# PCM2912_CODEC_MAIN.net
KiCad netlist of a schematic drawn in Altium Designer
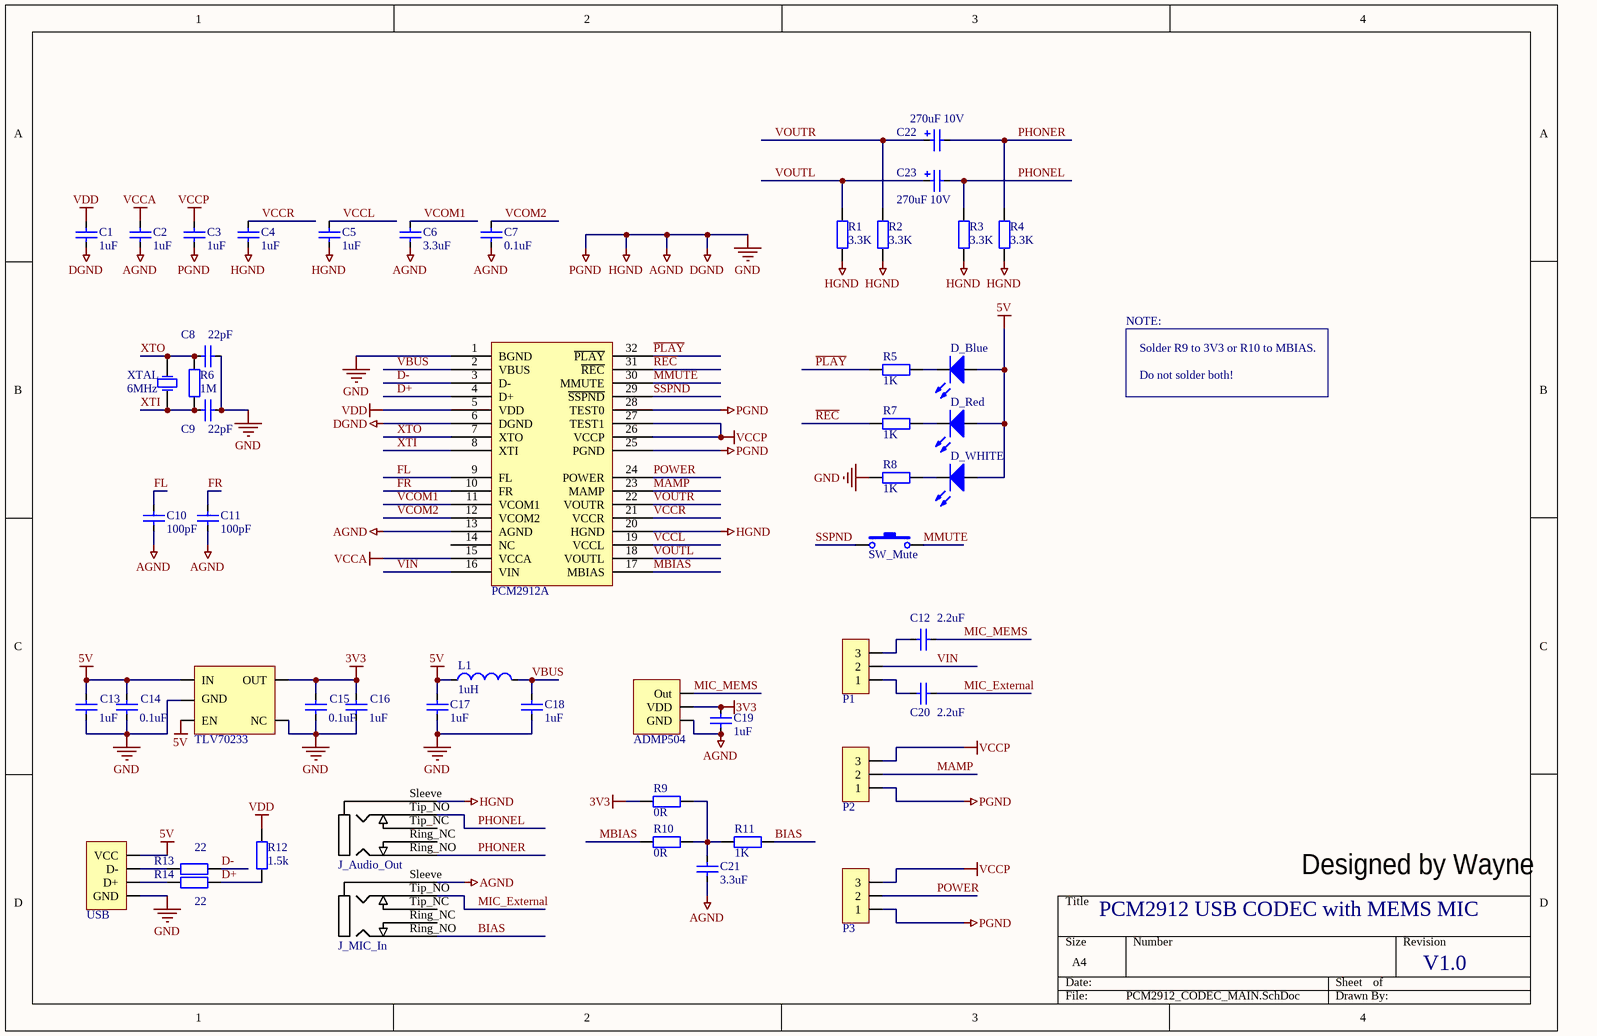
[diagram p0: PCM2912_CODEC_MAIN.SchDoc]

(export (version "E")
  (design (tool "Eeschema 10.0.6"))
  (components
    (comp (ref "ADMP504")
      (value "ADMP504")
      (footprint "PCB_IC:ADMP504")
      (description "ADMP504 Analog Output MEMS Microphone")
      (libsource (lib "SCH_IC") (part "ADMP504"))
    )
    (comp (ref "C1")
      (value "1uF")
      (footprint "PCB_Passive:CAP_0603")
      (description "Capacitor")
      (fields (field (name "Comment") "Cap_0603"))
      (libsource (lib "SCH_Passive") (part "Cap_0603"))
    )
    (comp (ref "C2")
      (value "1uF")
      (footprint "PCB_Passive:CAP_0603")
      (description "Capacitor")
      (fields (field (name "Comment") "Cap_0603"))
      (libsource (lib "SCH_Passive") (part "Cap_0603"))
    )
    (comp (ref "C3")
      (value "1uF")
      (footprint "PCB_Passive:CAP_0603")
      (description "Capacitor")
      (fields (field (name "Comment") "Cap_0603"))
      (libsource (lib "SCH_Passive") (part "Cap_0603"))
    )
    (comp (ref "C4")
      (value "1uF")
      (footprint "PCB_Passive:CAP_0603")
      (description "Capacitor")
      (fields (field (name "Comment") "Cap_0603"))
      (libsource (lib "SCH_Passive") (part "Cap_0603"))
    )
    (comp (ref "C5")
      (value "1uF")
      (footprint "PCB_Passive:CAP_0603")
      (description "Capacitor")
      (fields (field (name "Comment") "Cap_0603"))
      (libsource (lib "SCH_Passive") (part "Cap_0603"))
    )
    (comp (ref "C6")
      (value "3.3uF")
      (footprint "PCB_Passive:CAP_0603")
      (description "Capacitor")
      (fields (field (name "Comment") "Cap_0603"))
      (libsource (lib "SCH_Passive") (part "Cap_0603"))
    )
    (comp (ref "C7")
      (value "0.1uF")
      (footprint "PCB_Passive:CAP_0603")
      (description "Capacitor")
      (fields (field (name "Comment") "Cap_0603"))
      (libsource (lib "SCH_Passive") (part "Cap_0603"))
    )
    (comp (ref "C8")
      (value "22pF")
      (footprint "PCB_Passive:CAP_0603")
      (description "Capacitor")
      (fields (field (name "Comment") "Cap_0603"))
      (libsource (lib "SCH_Passive") (part "Cap_0603"))
    )
    (comp (ref "C9")
      (value "22pF")
      (footprint "PCB_Passive:CAP_0603")
      (description "Capacitor")
      (fields (field (name "Comment") "Cap_0603"))
      (libsource (lib "SCH_Passive") (part "Cap_0603"))
    )
    (comp (ref "C10")
      (value "100pF")
      (footprint "PCB_Passive:CAP_0603")
      (description "Capacitor")
      (fields (field (name "Comment") "Cap_0603"))
      (libsource (lib "SCH_Passive") (part "Cap_0603"))
    )
    (comp (ref "C11")
      (value "100pF")
      (footprint "PCB_Passive:CAP_0603")
      (description "Capacitor")
      (fields (field (name "Comment") "Cap_0603"))
      (libsource (lib "SCH_Passive") (part "Cap_0603"))
    )
    (comp (ref "C12")
      (value "2.2uF")
      (footprint "PCB_Passive:CAP_0603")
      (description "Capacitor")
      (fields (field (name "Comment") "Cap_0603"))
      (libsource (lib "SCH_Passive") (part "Cap_0603"))
    )
    (comp (ref "C13")
      (value "1uF")
      (footprint "PCB_Passive:CAP_0603")
      (description "Capacitor")
      (fields (field (name "Comment") "Cap_0603"))
      (libsource (lib "SCH_Passive") (part "Cap_0603"))
    )
    (comp (ref "C14")
      (value "0.1uF")
      (footprint "PCB_Passive:CAP_0603")
      (description "Capacitor")
      (fields (field (name "Comment") "Cap_0603"))
      (libsource (lib "SCH_Passive") (part "Cap_0603"))
    )
    (comp (ref "C15")
      (value "0.1uF")
      (footprint "PCB_Passive:CAP_0603")
      (description "Capacitor")
      (fields (field (name "Comment") "Cap_0603"))
      (libsource (lib "SCH_Passive") (part "Cap_0603"))
    )
    (comp (ref "C16")
      (value "1uF")
      (footprint "PCB_Passive:CAP_0603")
      (description "Capacitor")
      (fields (field (name "Comment") "Cap_0603"))
      (libsource (lib "SCH_Passive") (part "Cap_0603"))
    )
    (comp (ref "C17")
      (value "1uF")
      (footprint "PCB_Passive:CAP_0603")
      (description "Capacitor")
      (fields (field (name "Comment") "Cap_0603"))
      (libsource (lib "SCH_Passive") (part "Cap_0603"))
    )
    (comp (ref "C18")
      (value "1uF")
      (footprint "PCB_Passive:CAP_0603")
      (description "Capacitor")
      (fields (field (name "Comment") "Cap_0603"))
      (libsource (lib "SCH_Passive") (part "Cap_0603"))
    )
    (comp (ref "C19")
      (value "1uF")
      (footprint "PCB_Passive:CAP_0603")
      (description "Capacitor")
      (fields (field (name "Comment") "Cap_0603"))
      (libsource (lib "SCH_Passive") (part "Cap_0603"))
    )
    (comp (ref "C20")
      (value "2.2uF")
      (footprint "PCB_Passive:CAP_0603")
      (description "Capacitor")
      (fields (field (name "Comment") "Cap_0603"))
      (libsource (lib "SCH_Passive") (part "Cap_0603"))
    )
    (comp (ref "C21")
      (value "3.3uF")
      (footprint "PCB_Passive:CAP_0603")
      (description "Capacitor")
      (fields (field (name "Comment") "Cap_0603"))
      (libsource (lib "SCH_Passive") (part "Cap_0603"))
    )
    (comp (ref "C22")
      (value "270uF 10V")
      (footprint "PCB_Passive:CAP_ELEC_F3.5_D8_H11.5")
      (description "Cap_ELEC_8*11.5*3.5")
      (fields (field (name "Comment") "Capacitor"))
      (libsource (lib "SCH_Passive") (part "Cap_ELEC_8*11.5*3.5"))
    )
    (comp (ref "C23")
      (value "270uF 10V")
      (footprint "PCB_Passive:CAP_ELEC_F3.5_D8_H11.5")
      (description "Cap_ELEC_8*11.5*3.5")
      (fields (field (name "Comment") "Capacitor"))
      (libsource (lib "SCH_Passive") (part "Cap_ELEC_8*11.5*3.5"))
    )
    (comp (ref "D_Blue")
      (value "LED_0603_BLUE")
      (footprint "PCB_Active:LED_0603_BLUE")
      (description "LED")
      (libsource (lib "SCH_Active") (part "LED_0603_BLUE"))
    )
    (comp (ref "D_Red")
      (value "LED_0603_RED")
      (footprint "PCB_Active:LED_0603_RED")
      (description "LED")
      (libsource (lib "SCH_Active") (part "LED_0603_RED"))
    )
    (comp (ref "D_WHITE")
      (value "LED_0603_WHITE")
      (footprint "PCB_Active:LED_0603_WHITE")
      (description "LED")
      (libsource (lib "SCH_Active") (part "LED_0603_WHITE"))
    )
    (comp (ref "J_Audio_Out")
      (value "Generic 3.5 PhoneJack 5 Pin through-hole")
      (footprint "3.5 PhoneJack 5 Pin")
      (libsource (lib "SCH_Connector") (part "Generic 3.5 PhoneJack 5 Pin through-hole"))
    )
    (comp (ref "J_MIC_In")
      (value "Generic 3.5 PhoneJack 5 Pin through-hole")
      (footprint "3.5 PhoneJack 5 Pin")
      (libsource (lib "SCH_Connector") (part "Generic 3.5 PhoneJack 5 Pin through-hole"))
    )
    (comp (ref "L1")
      (value "1uH")
      (footprint "PCB_Passive:IND_0603")
      (description "Inductor")
      (fields (field (name "Comment") "Ind_0603"))
      (libsource (lib "SCH_Passive") (part "Ind_0603"))
    )
    (comp (ref "P1")
      (value "HDR1X3_90_2.54")
      (footprint "PCB_Connector:HDR1X3_90_2.54")
      (description "Header")
      (libsource (lib "SCH_Connector") (part "HDR1X3_90_2.54"))
    )
    (comp (ref "P2")
      (value "HDR1X3_90_2.54")
      (footprint "PCB_Connector:HDR1X3_90_2.54")
      (description "Header")
      (libsource (lib "SCH_Connector") (part "HDR1X3_90_2.54"))
    )
    (comp (ref "P3")
      (value "HDR1X3_90_2.54")
      (footprint "PCB_Connector:HDR1X3_90_2.54")
      (description "Header")
      (libsource (lib "SCH_Connector") (part "HDR1X3_90_2.54"))
    )
    (comp (ref "PCM2912A")
      (value "PCM2912A")
      (footprint "PCB_IC:TI-S-PQFP-N32")
      (description "PCM2912A USB CODEC")
      (libsource (lib "SCH_IC") (part "PCM2912A"))
    )
    (comp (ref "R1")
      (value "3.3K")
      (footprint "PCB_Passive:RES_0603")
      (description "Resistor")
      (fields (field (name "Comment") "Res_0603"))
      (libsource (lib "SCH_Passive") (part "Res_0603"))
    )
    (comp (ref "R2")
      (value "3.3K")
      (footprint "PCB_Passive:RES_0603")
      (description "Resistor")
      (fields (field (name "Comment") "Res_0603"))
      (libsource (lib "SCH_Passive") (part "Res_0603"))
    )
    (comp (ref "R3")
      (value "3.3K")
      (footprint "PCB_Passive:RES_0603")
      (description "Resistor")
      (fields (field (name "Comment") "Res_0603"))
      (libsource (lib "SCH_Passive") (part "Res_0603"))
    )
    (comp (ref "R4")
      (value "3.3K")
      (footprint "PCB_Passive:RES_0603")
      (description "Resistor")
      (fields (field (name "Comment") "Res_0603"))
      (libsource (lib "SCH_Passive") (part "Res_0603"))
    )
    (comp (ref "R5")
      (value "1K")
      (footprint "PCB_Passive:RES_0603")
      (description "Resistor")
      (fields (field (name "Comment") "Res_0603"))
      (libsource (lib "") (part "Res_0603_2"))
    )
    (comp (ref "R6")
      (value "1M")
      (footprint "PCB_Passive:RES_0603")
      (description "Resistor")
      (fields (field (name "Comment") "Res_0603"))
      (libsource (lib "SCH_Passive") (part "Res_0603"))
    )
    (comp (ref "R7")
      (value "1K")
      (footprint "PCB_Passive:RES_0603")
      (description "Resistor")
      (fields (field (name "Comment") "Res_0603"))
      (libsource (lib "") (part "Res_0603_2"))
    )
    (comp (ref "R8")
      (value "1K")
      (footprint "PCB_Passive:RES_0603")
      (description "Resistor")
      (fields (field (name "Comment") "Res_0603"))
      (libsource (lib "") (part "Res_0603_2"))
    )
    (comp (ref "R9")
      (value "0R")
      (footprint "PCB_Passive:RES_0603")
      (description "Resistor")
      (fields (field (name "Comment") "Res_0603"))
      (libsource (lib "") (part "Res_0603_1"))
    )
    (comp (ref "R10")
      (value "0R")
      (footprint "PCB_Passive:RES_0603")
      (description "Resistor")
      (fields (field (name "Comment") "Res_0603"))
      (libsource (lib "") (part "Res_0603_1"))
    )
    (comp (ref "R11")
      (value "1K")
      (footprint "PCB_Passive:RES_0603")
      (description "Resistor")
      (fields (field (name "Comment") "Res_0603"))
      (libsource (lib "") (part "Res_0603_2"))
    )
    (comp (ref "R12")
      (value "1.5k")
      (footprint "PCB_Passive:RES_0603")
      (description "Resistor")
      (fields (field (name "Comment") "Res_0603"))
      (libsource (lib "SCH_Passive") (part "Res_0603"))
    )
    (comp (ref "R13")
      (value "22")
      (footprint "PCB_Passive:RES_0603")
      (description "Resistor")
      (fields (field (name "Comment") "Res_0603"))
      (libsource (lib "") (part "Res_0603_1"))
    )
    (comp (ref "R14")
      (value "22")
      (footprint "PCB_Passive:RES_0603")
      (description "Resistor")
      (fields (field (name "Comment") "Res_0603"))
      (libsource (lib "") (part "Res_0603_1"))
    )
    (comp (ref "SW_Mute")
      (value "TACT Swtich SMT 6*6")
      (footprint "PCB_Switch:TACT Switch SMT 6*6")
      (libsource (lib "SCH_Switch") (part "TACT Swtich SMT 6*6"))
    )
    (comp (ref "TLV70233")
      (value "TLV70233")
      (footprint "PCB_IC:SOT23-5")
      (description "300mA LDO SOT-23")
      (libsource (lib "SCH_IC") (part "TLV70233"))
    )
    (comp (ref "USB") (value "USB") (footprint "PCB_USB:USB") (libsource (lib "SCH_USB") (part "USB")))
    (comp (ref "XTAL")
      (value "6MHz")
      (footprint "PCB_Oscillator:XTAL_5032")
      (description "Crystal Oscillator")
      (fields (field (name "Comment") "XTAL_5032") (field (name "PUBLISHER") "Altium Limited"))
      (libsource (lib "SCH_Oscillator") (part "XTAL_5032"))
    )
  )
  (nets
    (net (code "1") (name "/BIAS") (class "Default")
      (node (ref "J_MIC_In") (pin "Ring_NO") (pinfunction "Ring_NO_Ring_NO") (pintype "passive"))
      (node (ref "R11") (pin "1") (pinfunction "1_1") (pintype "passive"))
    )
    (net (code "2") (name "/D+") (class "Default")
      (node (ref "PCM2912A") (pin "4") (pinfunction "D+_4") (pintype "passive"))
      (node (ref "R12") (pin "2") (pinfunction "2_2") (pintype "passive"))
      (node (ref "R14") (pin "2") (pinfunction "2_2") (pintype "passive"))
    )
    (net (code "3") (name "/D-") (class "Default")
      (node (ref "PCM2912A") (pin "3") (pinfunction "D-_3") (pintype "passive"))
      (node (ref "R13") (pin "2") (pinfunction "2_2") (pintype "passive"))
    )
    (net (code "4") (name "/FL") (class "Default")
      (node (ref "C10") (pin "2") (pinfunction "2_2") (pintype "passive"))
      (node (ref "PCM2912A") (pin "9") (pinfunction "FL_9") (pintype "passive"))
    )
    (net (code "5") (name "/FR") (class "Default")
      (node (ref "C11") (pin "2") (pinfunction "2_2") (pintype "passive"))
      (node (ref "PCM2912A") (pin "10") (pinfunction "FR_10") (pintype "passive"))
    )
    (net (code "6") (name "/MAMP") (class "Default")
      (node (ref "P2") (pin "2") (pinfunction "2_2") (pintype "passive"))
      (node (ref "PCM2912A") (pin "23") (pinfunction "MAMP_23") (pintype "passive"))
    )
    (net (code "7") (name "/MBIAS") (class "Default")
      (node (ref "PCM2912A") (pin "17") (pinfunction "MBIAS_17") (pintype "passive"))
      (node (ref "R10") (pin "1") (pinfunction "1_1") (pintype "passive"))
    )
    (net (code "8") (name "/MIC_External") (class "Default")
      (node (ref "C20") (pin "2") (pinfunction "2_2") (pintype "passive"))
      (node (ref "J_MIC_In") (pin "Tip_NO") (pinfunction "Tip_NO_Tip_NO") (pintype "passive"))
    )
    (net (code "9") (name "/MIC_MEMS") (class "Default")
      (node (ref "ADMP504") (pin "1") (pinfunction "Out_1") (pintype "passive"))
      (node (ref "C12") (pin "2") (pinfunction "2_2") (pintype "passive"))
    )
    (net (code "10") (name "/MMUTE") (class "Default")
      (node (ref "PCM2912A") (pin "30") (pinfunction "MMUTE_30") (pintype "passive"))
      (node (ref "SW_Mute") (pin "2") (pinfunction "2_2") (pintype "passive"))
    )
    (net (code "11") (name "/PHONEL") (class "Default")
      (node (ref "C23") (pin "2") (pinfunction "2_2") (pintype "passive"))
      (node (ref "J_Audio_Out") (pin "Tip_NO") (pinfunction "Tip_NO_Tip_NO") (pintype "passive"))
      (node (ref "R3") (pin "1") (pinfunction "1_1") (pintype "passive"))
    )
    (net (code "12") (name "/PHONER") (class "Default")
      (node (ref "C22") (pin "2") (pinfunction "2_2") (pintype "passive"))
      (node (ref "J_Audio_Out") (pin "Ring_NO") (pinfunction "Ring_NO_Ring_NO") (pintype "passive"))
      (node (ref "R4") (pin "1") (pinfunction "1_1") (pintype "passive"))
    )
    (net (code "13") (name "/POWER") (class "Default")
      (node (ref "P3") (pin "2") (pinfunction "2_2") (pintype "passive"))
      (node (ref "PCM2912A") (pin "24") (pinfunction "POWER_24") (pintype "passive"))
    )
    (net (code "14") (name "/SSPND") (class "Default")
      (node (ref "PCM2912A") (pin "29") (pinfunction "~{SSPND}_29") (pintype "passive"))
      (node (ref "SW_Mute") (pin "1") (pinfunction "1_1") (pintype "passive"))
    )
    (net (code "15") (name "/VBUS") (class "Default")
      (node (ref "C18") (pin "2") (pinfunction "2_2") (pintype "passive"))
      (node (ref "L1") (pin "2") (pinfunction "2_2") (pintype "passive"))
      (node (ref "PCM2912A") (pin "2") (pinfunction "VBUS_2") (pintype "passive"))
    )
    (net (code "16") (name "/VCCL") (class "Default")
      (node (ref "C5") (pin "2") (pinfunction "2_2") (pintype "passive"))
      (node (ref "PCM2912A") (pin "19") (pinfunction "VCCL_19") (pintype "passive"))
    )
    (net (code "17") (name "/VCCR") (class "Default")
      (node (ref "C4") (pin "2") (pinfunction "2_2") (pintype "passive"))
      (node (ref "PCM2912A") (pin "21") (pinfunction "VCCR_21") (pintype "passive"))
    )
    (net (code "18") (name "/VCOM1") (class "Default")
      (node (ref "C6") (pin "2") (pinfunction "2_2") (pintype "passive"))
      (node (ref "PCM2912A") (pin "11") (pinfunction "VCOM1_11") (pintype "passive"))
    )
    (net (code "19") (name "/VCOM2") (class "Default")
      (node (ref "C7") (pin "2") (pinfunction "2_2") (pintype "passive"))
      (node (ref "PCM2912A") (pin "12") (pinfunction "VCOM2_12") (pintype "passive"))
    )
    (net (code "20") (name "/VIN") (class "Default")
      (node (ref "P1") (pin "2") (pinfunction "2_2") (pintype "passive"))
      (node (ref "PCM2912A") (pin "16") (pinfunction "VIN_16") (pintype "passive"))
    )
    (net (code "21") (name "/VOUTL") (class "Default")
      (node (ref "C23") (pin "1") (pinfunction "1_1") (pintype "passive"))
      (node (ref "PCM2912A") (pin "18") (pinfunction "VOUTL_18") (pintype "passive"))
      (node (ref "R1") (pin "1") (pinfunction "1_1") (pintype "passive"))
    )
    (net (code "22") (name "/VOUTR") (class "Default")
      (node (ref "C22") (pin "1") (pinfunction "1_1") (pintype "passive"))
      (node (ref "PCM2912A") (pin "22") (pinfunction "VOUTR_22") (pintype "passive"))
      (node (ref "R2") (pin "1") (pinfunction "1_1") (pintype "passive"))
    )
    (net (code "23") (name "/XTI") (class "Default")
      (node (ref "C9") (pin "2") (pinfunction "2_2") (pintype "passive"))
      (node (ref "PCM2912A") (pin "8") (pinfunction "XTI_8") (pintype "passive"))
      (node (ref "R6") (pin "2") (pinfunction "2_2") (pintype "passive"))
      (node (ref "XTAL") (pin "1") (pinfunction "OSC1_1") (pintype "passive"))
    )
    (net (code "24") (name "/XTO") (class "Default")
      (node (ref "C8") (pin "2") (pinfunction "2_2") (pintype "passive"))
      (node (ref "PCM2912A") (pin "7") (pinfunction "XTO_7") (pintype "passive"))
      (node (ref "R6") (pin "1") (pinfunction "1_1") (pintype "passive"))
      (node (ref "XTAL") (pin "2") (pinfunction "OSC2_2") (pintype "passive"))
    )
    (net (code "25") (name "/~{PLAY}") (class "Default")
      (node (ref "PCM2912A") (pin "32") (pinfunction "~{PLAY}_32") (pintype "passive"))
      (node (ref "R5") (pin "2") (pinfunction "2_2") (pintype "passive"))
    )
    (net (code "26") (name "/~{REC}") (class "Default")
      (node (ref "PCM2912A") (pin "31") (pinfunction "~{REC}_31") (pintype "passive"))
      (node (ref "R7") (pin "2") (pinfunction "2_2") (pintype "passive"))
    )
    (net (code "27") (name "3V3") (class "Default")
      (node (ref "ADMP504") (pin "3") (pinfunction "VDD_3") (pintype "passive"))
      (node (ref "C15") (pin "1") (pinfunction "1_1") (pintype "passive"))
      (node (ref "C16") (pin "1") (pinfunction "1_1") (pintype "passive"))
      (node (ref "C19") (pin "2") (pinfunction "2_2") (pintype "passive"))
      (node (ref "R9") (pin "1") (pinfunction "1_1") (pintype "passive"))
      (node (ref "TLV70233") (pin "5") (pinfunction "OUT_5") (pintype "power_in"))
    )
    (net (code "28") (name "5V") (class "Default")
      (node (ref "C13") (pin "1") (pinfunction "1_1") (pintype "passive"))
      (node (ref "C14") (pin "1") (pinfunction "1_1") (pintype "passive"))
      (node (ref "C17") (pin "2") (pinfunction "2_2") (pintype "passive"))
      (node (ref "D_Blue") (pin "1") (pinfunction "A_1") (pintype "passive"))
      (node (ref "D_Red") (pin "1") (pinfunction "A_1") (pintype "passive"))
      (node (ref "D_WHITE") (pin "1") (pinfunction "A_1") (pintype "passive"))
      (node (ref "L1") (pin "1") (pinfunction "1_1") (pintype "passive"))
      (node (ref "TLV70233") (pin "1") (pinfunction "IN_1") (pintype "power_in"))
      (node (ref "TLV70233") (pin "3") (pinfunction "EN_3") (pintype "passive"))
      (node (ref "USB") (pin "1") (pinfunction "VCC_1") (pintype "passive"))
    )
    (net (code "29") (name "AGND") (class "Default")
      (node (ref "ADMP504") (pin "2") (pinfunction "GND_2") (pintype "passive"))
      (node (ref "C1") (pin "1") (pinfunction "1_1") (pintype "passive"))
      (node (ref "C10") (pin "1") (pinfunction "1_1") (pintype "passive"))
      (node (ref "C11") (pin "1") (pinfunction "1_1") (pintype "passive"))
      (node (ref "C13") (pin "2") (pinfunction "2_2") (pintype "passive"))
      (node (ref "C14") (pin "2") (pinfunction "2_2") (pintype "passive"))
      (node (ref "C15") (pin "2") (pinfunction "2_2") (pintype "passive"))
      (node (ref "C16") (pin "2") (pinfunction "2_2") (pintype "passive"))
      (node (ref "C17") (pin "1") (pinfunction "1_1") (pintype "passive"))
      (node (ref "C18") (pin "1") (pinfunction "1_1") (pintype "passive"))
      (node (ref "C19") (pin "1") (pinfunction "1_1") (pintype "passive"))
      (node (ref "C2") (pin "1") (pinfunction "1_1") (pintype "passive"))
      (node (ref "C21") (pin "1") (pinfunction "1_1") (pintype "passive"))
      (node (ref "C3") (pin "1") (pinfunction "1_1") (pintype "passive"))
      (node (ref "C4") (pin "1") (pinfunction "1_1") (pintype "passive"))
      (node (ref "C5") (pin "1") (pinfunction "1_1") (pintype "passive"))
      (node (ref "C6") (pin "1") (pinfunction "1_1") (pintype "passive"))
      (node (ref "C7") (pin "1") (pinfunction "1_1") (pintype "passive"))
      (node (ref "C8") (pin "1") (pinfunction "1_1") (pintype "passive"))
      (node (ref "C9") (pin "1") (pinfunction "1_1") (pintype "passive"))
      (node (ref "J_Audio_Out") (pin "Sleeve") (pinfunction "Sleeve_Sleeve") (pintype "passive"))
      (node (ref "J_MIC_In") (pin "Sleeve") (pinfunction "Sleeve_Sleeve") (pintype "passive"))
      (node (ref "P2") (pin "1") (pinfunction "1_1") (pintype "passive"))
      (node (ref "P3") (pin "1") (pinfunction "1_1") (pintype "passive"))
      (node (ref "PCM2912A") (pin "1") (pinfunction "BGND_1") (pintype "passive"))
      (node (ref "PCM2912A") (pin "13") (pinfunction "AGND_13") (pintype "passive"))
      (node (ref "PCM2912A") (pin "20") (pinfunction "HGND_20") (pintype "passive"))
      (node (ref "PCM2912A") (pin "25") (pinfunction "PGND_25") (pintype "passive"))
      (node (ref "PCM2912A") (pin "28") (pinfunction "TEST0_28") (pintype "passive"))
      (node (ref "PCM2912A") (pin "6") (pinfunction "DGND_6") (pintype "passive"))
      (node (ref "R1") (pin "2") (pinfunction "2_2") (pintype "passive"))
      (node (ref "R2") (pin "2") (pinfunction "2_2") (pintype "passive"))
      (node (ref "R3") (pin "2") (pinfunction "2_2") (pintype "passive"))
      (node (ref "R4") (pin "2") (pinfunction "2_2") (pintype "passive"))
      (node (ref "R8") (pin "2") (pinfunction "2_2") (pintype "passive"))
      (node (ref "TLV70233") (pin "2") (pinfunction "GND_2") (pintype "power_in"))
      (node (ref "TLV70233") (pin "4") (pinfunction "NC_4") (pintype "power_in"))
      (node (ref "USB") (pin "4") (pinfunction "GND_4") (pintype "passive"))
    )
    (net (code "30") (name "Net-(C12-Pad1)") (class "Default")
      (node (ref "C12") (pin "1") (pinfunction "1_1") (pintype "passive"))
      (node (ref "P1") (pin "3") (pinfunction "3_3") (pintype "passive"))
    )
    (net (code "31") (name "Net-(C20-Pad1)") (class "Default")
      (node (ref "C20") (pin "1") (pinfunction "1_1") (pintype "passive"))
      (node (ref "P1") (pin "1") (pinfunction "1_1") (pintype "passive"))
    )
    (net (code "32") (name "Net-(C21-Pad2)") (class "Default")
      (node (ref "C21") (pin "2") (pinfunction "2_2") (pintype "passive"))
      (node (ref "R10") (pin "2") (pinfunction "2_2") (pintype "passive"))
      (node (ref "R11") (pin "2") (pinfunction "2_2") (pintype "passive"))
      (node (ref "R9") (pin "2") (pinfunction "2_2") (pintype "passive"))
    )
    (net (code "33") (name "Net-(D_Blue-K)") (class "Default")
      (node (ref "D_Blue") (pin "2") (pinfunction "K_2") (pintype "passive"))
      (node (ref "R5") (pin "1") (pinfunction "1_1") (pintype "passive"))
    )
    (net (code "34") (name "Net-(D_Red-K)") (class "Default")
      (node (ref "D_Red") (pin "2") (pinfunction "K_2") (pintype "passive"))
      (node (ref "R7") (pin "1") (pinfunction "1_1") (pintype "passive"))
    )
    (net (code "35") (name "Net-(D_WHITE-K)") (class "Default")
      (node (ref "D_WHITE") (pin "2") (pinfunction "K_2") (pintype "passive"))
      (node (ref "R8") (pin "1") (pinfunction "1_1") (pintype "passive"))
    )
    (net (code "36") (name "Net-(USB-D+)") (class "Default")
      (node (ref "R14") (pin "1") (pinfunction "1_1") (pintype "passive"))
      (node (ref "USB") (pin "3") (pinfunction "D+_3") (pintype "passive"))
    )
    (net (code "37") (name "Net-(USB-D-)") (class "Default")
      (node (ref "R13") (pin "1") (pinfunction "1_1") (pintype "passive"))
      (node (ref "USB") (pin "2") (pinfunction "D-_2") (pintype "passive"))
    )
    (net (code "38") (name "VCCA") (class "Default")
      (node (ref "C2") (pin "2") (pinfunction "2_2") (pintype "passive"))
      (node (ref "PCM2912A") (pin "15") (pinfunction "VCCA_15") (pintype "passive"))
    )
    (net (code "39") (name "VCCP") (class "Default")
      (node (ref "C3") (pin "2") (pinfunction "2_2") (pintype "passive"))
      (node (ref "P2") (pin "3") (pinfunction "3_3") (pintype "passive"))
      (node (ref "P3") (pin "3") (pinfunction "3_3") (pintype "passive"))
      (node (ref "PCM2912A") (pin "26") (pinfunction "VCCP_26") (pintype "passive"))
      (node (ref "PCM2912A") (pin "27") (pinfunction "TEST1_27") (pintype "passive"))
    )
    (net (code "40") (name "VDD") (class "Default")
      (node (ref "C1") (pin "2") (pinfunction "2_2") (pintype "passive"))
      (node (ref "PCM2912A") (pin "5") (pinfunction "VDD_5") (pintype "passive"))
      (node (ref "R12") (pin "1") (pinfunction "1_1") (pintype "passive"))
    )
    (net (code "41") (name "unconnected-(J_Audio_Out-PadRing_NC)") (class "Default")
      (node (ref "J_Audio_Out") (pin "Ring_NC") (pinfunction "Ring_NC_Ring_NC") (pintype "passive"))
    )
    (net (code "42") (name "unconnected-(J_Audio_Out-PadTip_NC)") (class "Default")
      (node (ref "J_Audio_Out") (pin "Tip_NC") (pinfunction "Tip_NC_Tip_NC") (pintype "passive"))
    )
    (net (code "43") (name "unconnected-(J_MIC_In-PadRing_NC)") (class "Default")
      (node (ref "J_MIC_In") (pin "Ring_NC") (pinfunction "Ring_NC_Ring_NC") (pintype "passive"))
    )
    (net (code "44") (name "unconnected-(J_MIC_In-PadTip_NC)") (class "Default")
      (node (ref "J_MIC_In") (pin "Tip_NC") (pinfunction "Tip_NC_Tip_NC") (pintype "passive"))
    )
    (net (code "45") (name "unconnected-(PCM2912A-NC-Pad14)") (class "Default")
      (node (ref "PCM2912A") (pin "14") (pinfunction "NC_14") (pintype "passive"))
    )
  )
)
